# display-lcd-16x2.net
KiCad netlist of a schematic drawn in Altium Designer
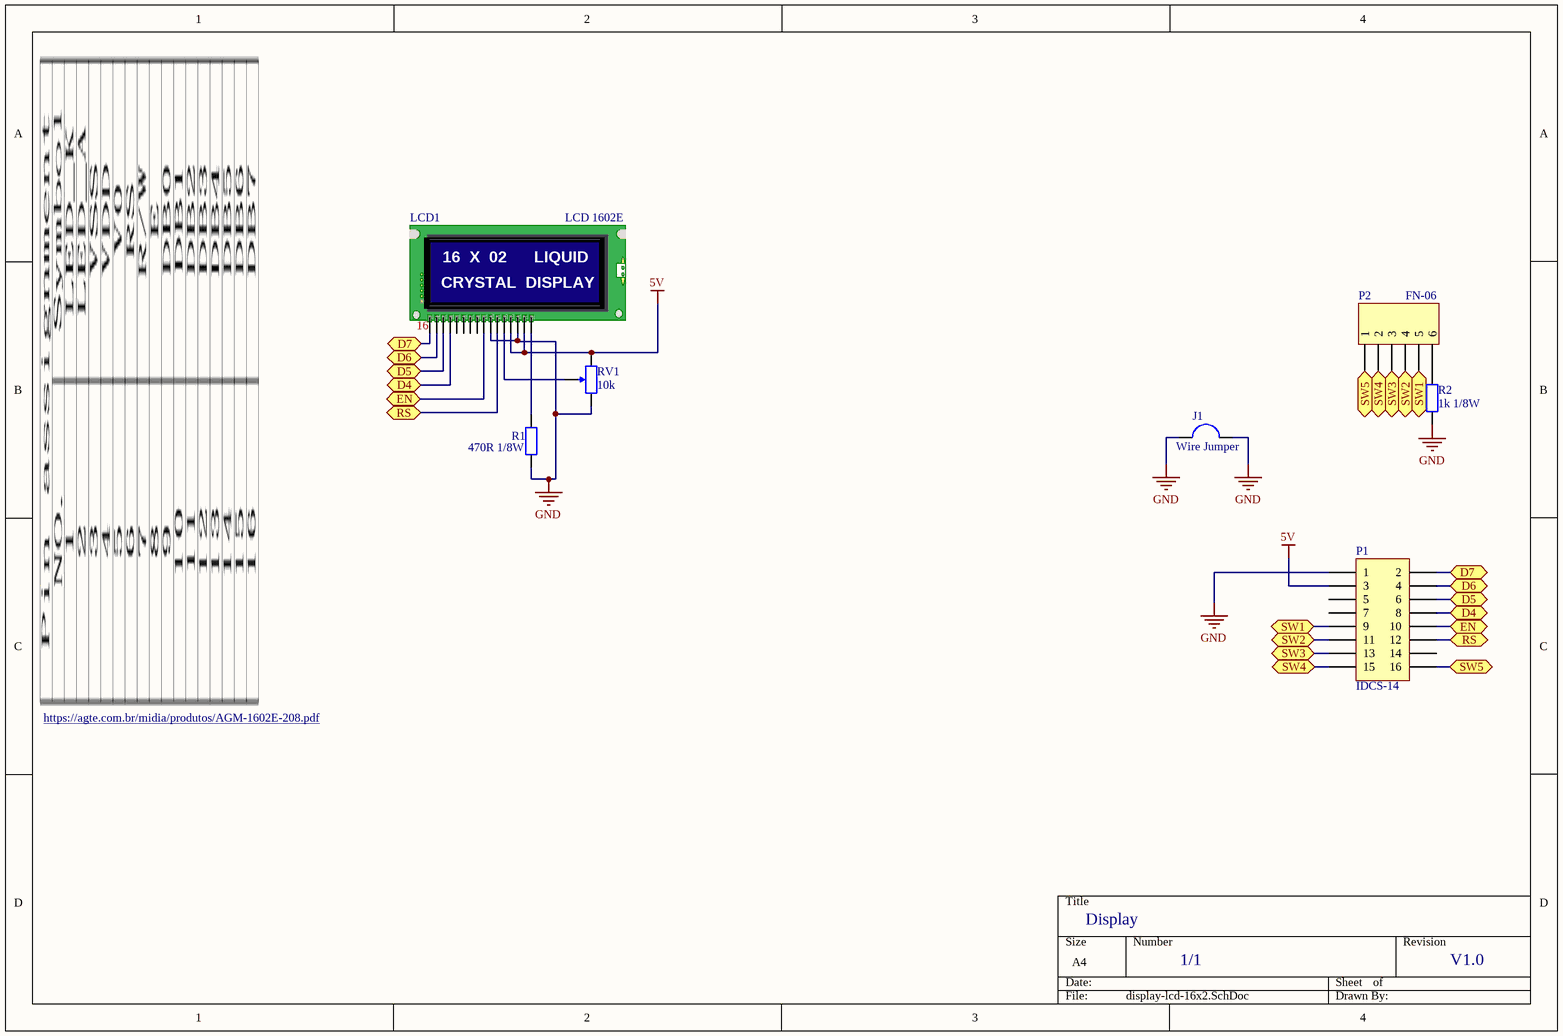
[diagram p0: display-lcd-16x2.SchDoc]

(export (version "E")
  (design (tool "Eeschema 10.0.6"))
  (components
    (comp (ref "J1")
      (value "Wire Jumper")
      (footprint "Lib PTH:JUMPER CR16")
      (description "JUMPER 7,62MM")
      (fields
        (field (name "MANUFACTURER") "Stackpole Electronics Inc.")
        (field (name "MANUFACTURER PART NUMBER") "JW60ZT0R00")
      )
      (libsource (lib "Lib PTH") (part "Jumper CR16"))
    )
    (comp (ref "LCD1")
      (value "LCD 1602E")
      (footprint "LCD1602B")
      (description "LCD ALPHA/NUM DISPL 16X2 BLU/WHT")
      (fields (field (name "MANUFACTURER") "AGTechonogies") (field (name "PART NUMBER") "AGM 1602B-802"))
      (libsource (lib "Biblioteca_pth") (part "LCD 1602 Azul"))
    )
    (comp (ref "P1")
      (value "IDCS-14")
      (footprint "IDCSC-16")
      (description "Header, 8-Pin, Dual row")
      (fields (field (name "PUBLISHER") "Altium Limited"))
      (libsource (lib "Miscellaneous Connectors") (part "Header 8X2"))
    )
    (comp (ref "P2")
      (value "FN-06")
      (footprint "FN-06")
      (description "CONN FFC FPC TOP 6POS 2.54MM R/A")
      (fields
        (field (name "MANUFACTURER") "TE Connectivity AMP Connectors")
        (field (name "MANUFACTURER PART NUMBER") "5-520314-6")
      )
      (libsource (lib "Biblioteca_pth") (part "Conector para PCI flexível"))
    )
    (comp (ref "R1")
      (value "470R 1/8W")
      (footprint "RESISTOR_CR16")
      (description "RES 470 OHM 1/8W 5% CF AXIAL CARBON FILM")
      (fields
        (field (name "MANUFACTURER") "Stackpole Electronics Inc")
        (field (name "MANUFACTURER PART NUMBER") "CF18JT470R")
      )
      (libsource (lib "Biblioteca_pth") (part "Res 470R 1/8W 5%"))
    )
    (comp (ref "R2")
      (value "1k 1/8W")
      (footprint "Lib PTH:RES CR16")
      (description "RES 1k OHM 1/8W 5% AXIAL")
      (fields
        (field (name "MANUFACTURER") "Stackpole Electronics Inc.")
        (field (name "MANUFACTURER PART NUMBER") "CF18JT1K00")
      )
      (libsource (lib "Lib PTH") (part "Res 1k 1/8W 5% CR16"))
    )
    (comp (ref "RV1")
      (value "10k")
      (footprint "3296W")
      (description "Trimmer 3296W-1-103LF")
      (fields (field (name "MANUFACTURER") "Bourns Inc.") (field (name "TOLERANCE") "±10%"))
      (libsource (lib "Lib PTH") (part "Trimmer 3296W-1-103LF"))
    )
  )
  (nets
    (net (code "1") (name "/D4") (class "Default")
      (node (ref "LCD1") (pin "11") (pinfunction "11_11") (pintype "passive"))
      (node (ref "P1") (pin "8") (pinfunction "8_8") (pintype "passive"))
    )
    (net (code "2") (name "/D5") (class "Default")
      (node (ref "LCD1") (pin "12") (pinfunction "12_12") (pintype "passive"))
      (node (ref "P1") (pin "6") (pinfunction "6_6") (pintype "passive"))
    )
    (net (code "3") (name "/D6") (class "Default")
      (node (ref "LCD1") (pin "13") (pinfunction "13_13") (pintype "passive"))
      (node (ref "P1") (pin "4") (pinfunction "4_4") (pintype "passive"))
    )
    (net (code "4") (name "/D7") (class "Default")
      (node (ref "LCD1") (pin "14") (pinfunction "14_14") (pintype "passive"))
      (node (ref "P1") (pin "2") (pinfunction "2_2") (pintype "passive"))
    )
    (net (code "5") (name "/EN") (class "Default")
      (node (ref "LCD1") (pin "6") (pinfunction "6_6") (pintype "passive"))
      (node (ref "P1") (pin "10") (pinfunction "10_10") (pintype "passive"))
    )
    (net (code "6") (name "/RS") (class "Default")
      (node (ref "LCD1") (pin "4") (pinfunction "4_4") (pintype "passive"))
      (node (ref "P1") (pin "12") (pinfunction "12_12") (pintype "passive"))
    )
    (net (code "7") (name "/SW1") (class "Default")
      (node (ref "P1") (pin "9") (pinfunction "9_9") (pintype "passive"))
      (node (ref "P2") (pin "5") (pinfunction "5_5") (pintype "passive"))
    )
    (net (code "8") (name "/SW2") (class "Default")
      (node (ref "P1") (pin "11") (pinfunction "11_11") (pintype "passive"))
      (node (ref "P2") (pin "4") (pinfunction "4_4") (pintype "passive"))
    )
    (net (code "9") (name "/SW3") (class "Default")
      (node (ref "P1") (pin "13") (pinfunction "13_13") (pintype "passive"))
      (node (ref "P2") (pin "3") (pinfunction "3_3") (pintype "passive"))
    )
    (net (code "10") (name "/SW4") (class "Default")
      (node (ref "P1") (pin "15") (pinfunction "15_15") (pintype "passive"))
      (node (ref "P2") (pin "2") (pinfunction "2_2") (pintype "passive"))
    )
    (net (code "11") (name "/SW5") (class "Default")
      (node (ref "P1") (pin "16") (pinfunction "16_16") (pintype "passive"))
      (node (ref "P2") (pin "1") (pinfunction "1_1") (pintype "passive"))
    )
    (net (code "12") (name "5V") (class "Default")
      (node (ref "LCD1") (pin "15") (pinfunction "15_15") (pintype "passive"))
      (node (ref "LCD1") (pin "2") (pinfunction "2_2") (pintype "passive"))
      (node (ref "P1") (pin "3") (pinfunction "3_3") (pintype "passive"))
      (node (ref "RV1") (pin "1") (pinfunction "TOP_1") (pintype "passive"))
    )
    (net (code "13") (name "GND") (class "Default")
      (node (ref "J1") (pin "1") (pinfunction "1_1") (pintype "passive"))
      (node (ref "J1") (pin "2") (pinfunction "2_2") (pintype "passive"))
      (node (ref "LCD1") (pin "1") (pinfunction "1_1") (pintype "passive"))
      (node (ref "LCD1") (pin "5") (pinfunction "5_5") (pintype "passive"))
      (node (ref "P1") (pin "1") (pinfunction "1_1") (pintype "passive"))
      (node (ref "R1") (pin "1") (pinfunction "1_1") (pintype "passive"))
      (node (ref "R2") (pin "1") (pinfunction "1_1") (pintype "passive"))
      (node (ref "RV1") (pin "3") (pinfunction "BOT_3") (pintype "passive"))
    )
    (net (code "14") (name "Net-(LCD1-Pad16)") (class "Default")
      (node (ref "LCD1") (pin "16") (pinfunction "16_16") (pintype "passive"))
      (node (ref "R1") (pin "2") (pinfunction "2_2") (pintype "passive"))
    )
    (net (code "15") (name "Net-(P2-Pad6)") (class "Default")
      (node (ref "P2") (pin "6") (pinfunction "6_6") (pintype "passive"))
      (node (ref "R2") (pin "2") (pinfunction "2_2") (pintype "passive"))
    )
    (net (code "16") (name "Net-(RV1-TAP)") (class "Default")
      (node (ref "LCD1") (pin "3") (pinfunction "3_3") (pintype "passive"))
      (node (ref "RV1") (pin "2") (pinfunction "TAP_2") (pintype "passive"))
    )
    (net (code "17") (name "unconnected-(LCD1-Pad7)") (class "Default")
      (node (ref "LCD1") (pin "7") (pinfunction "7_7") (pintype "passive"))
    )
    (net (code "18") (name "unconnected-(LCD1-Pad8)") (class "Default")
      (node (ref "LCD1") (pin "8") (pinfunction "8_8") (pintype "passive"))
    )
    (net (code "19") (name "unconnected-(LCD1-Pad9)") (class "Default")
      (node (ref "LCD1") (pin "9") (pinfunction "9_9") (pintype "passive"))
    )
    (net (code "20") (name "unconnected-(LCD1-Pad10)") (class "Default")
      (node (ref "LCD1") (pin "10") (pinfunction "10_10") (pintype "passive"))
    )
    (net (code "21") (name "unconnected-(P1-Pad5)") (class "Default")
      (node (ref "P1") (pin "5") (pinfunction "5_5") (pintype "passive"))
    )
    (net (code "22") (name "unconnected-(P1-Pad7)") (class "Default")
      (node (ref "P1") (pin "7") (pinfunction "7_7") (pintype "passive"))
    )
    (net (code "23") (name "unconnected-(P1-Pad14)") (class "Default")
      (node (ref "P1") (pin "14") (pinfunction "14_14") (pintype "passive"))
    )
  )
)
